# Phase_Measurements.net
KiCad netlist of a schematic drawn in Altium Designer
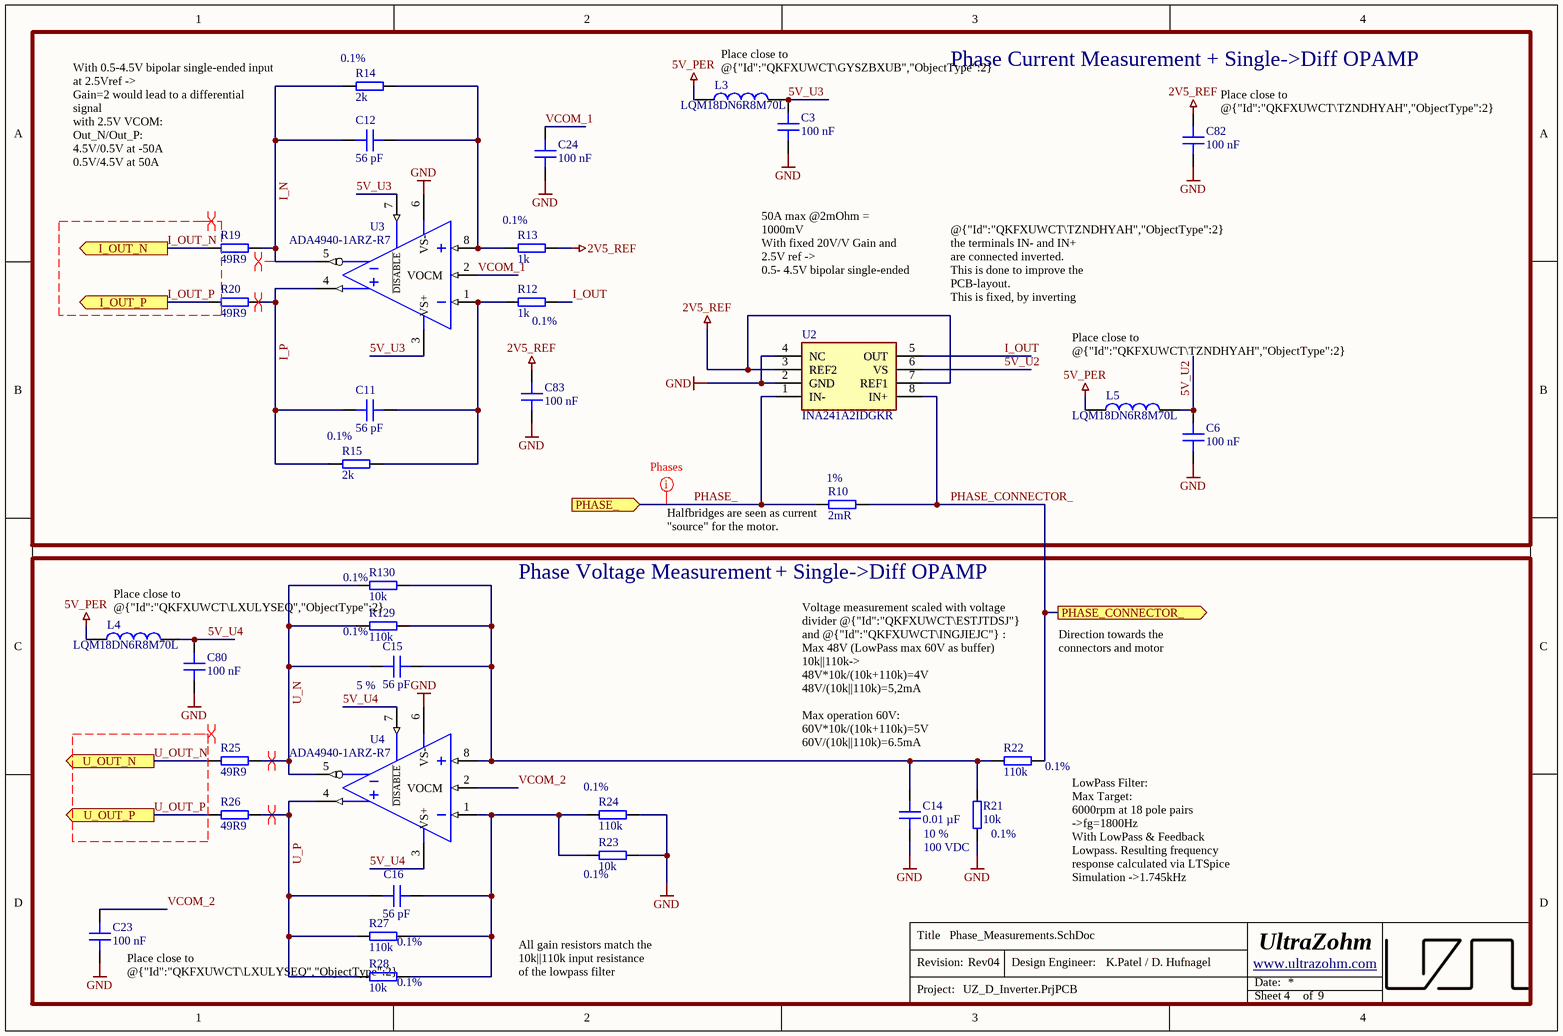
[diagram p0: Phase_Measurements.SchDoc]

(export (version "E")
  (design (tool "Eeschema 10.0.6"))
  (components
    (comp (ref "C3")
      (value "100 nF")
      (footprint "C_0603")
      (description "100V 100nF X7S ±10% 0603 Multilayer Ceramic Capacitors MLCC - SMD/SMT ROHS")
      (fields
        (field (name "MANUFACTURER PART NUMBER") "C1608X7S2A104KT000N")
        (field (name "MANUFACTURER") "TDK")
        (field (name "CREATED FROM") "AGeiger")
      )
      (libsource (lib "user") (part "Capacitor"))
    )
    (comp (ref "C6")
      (value "100 nF")
      (footprint "C_0603")
      (description "100V 100nF X7S ±10% 0603 Multilayer Ceramic Capacitors MLCC - SMD/SMT ROHS")
      (fields
        (field (name "MANUFACTURER PART NUMBER") "C1608X7S2A104KT000N")
        (field (name "MANUFACTURER") "TDK")
        (field (name "CREATED FROM") "AGeiger")
      )
      (libsource (lib "user") (part "Capacitor"))
    )
    (comp (ref "C11")
      (value "56 pF")
      (footprint "C_0603")
      (description "Capacitor 0603, 50 VDC, 56 pF, C0G")
      (fields
        (field (name "MANUFACTURER PART NUMBER") "CL10C560JB8NNNC")
        (field (name "MANUFACTURER") "Samsung Electro-Mechanics")
        (field (name "CREATED FROM") "DHufnagel")
      )
      (libsource (lib "user") (part "Capacitor"))
    )
    (comp (ref "C12")
      (value "56 pF")
      (footprint "C_0603")
      (description "Capacitor 0603, 50 VDC, 56 pF, C0G")
      (fields
        (field (name "MANUFACTURER PART NUMBER") "CL10C560JB8NNNC")
        (field (name "MANUFACTURER") "Samsung Electro-Mechanics")
        (field (name "CREATED FROM") "DHufnagel")
      )
      (libsource (lib "user") (part "Capacitor"))
    )
    (comp (ref "C14")
      (value "0.01 µF")
      (footprint "C_0805")
      (description "100V 10nF 0805 Multilayer Ceramic Capacitors MLCC - SMD/SMT ROHS")
      (fields
        (field (name "MANUFACTURER PART NUMBER") "HV0805X7R103K101NT")
        (field (name "MANUFACTURER") "AIDE")
        (field (name "TOLERANCE") "10 %")
        (field (name "VOLTAGE RATING") "100 VDC")
        (field (name "CREATED FROM") "KIlhan")
      )
      (libsource (lib "user") (part "Capacitor"))
    )
    (comp (ref "C15")
      (value "56 pF")
      (footprint "C_0603")
      (description "Capacitor 0603, 50 VDC, 56 pF, C0G")
      (fields
        (field (name "MANUFACTURER PART NUMBER") "CL10C560JB8NNNC")
        (field (name "MANUFACTURER") "Samsung Electro-Mechanics")
        (field (name "TOLERANCE") "5 %")
        (field (name "CREATED FROM") "DHufnagel")
      )
      (libsource (lib "user") (part "Capacitor"))
    )
    (comp (ref "C16")
      (value "56 pF")
      (footprint "C_0603")
      (description "Capacitor 0603, 50 VDC, 56 pF, C0G")
      (fields
        (field (name "MANUFACTURER PART NUMBER") "CL10C560JB8NNNC")
        (field (name "MANUFACTURER") "Samsung Electro-Mechanics")
        (field (name "CREATED FROM") "DHufnagel")
      )
      (libsource (lib "user") (part "Capacitor"))
    )
    (comp (ref "C23")
      (value "100 nF")
      (footprint "C_0603")
      (description "100V 100nF X7S ±10% 0603 Multilayer Ceramic Capacitors MLCC - SMD/SMT ROHS")
      (fields
        (field (name "MANUFACTURER PART NUMBER") "C1608X7S2A104KT000N")
        (field (name "MANUFACTURER") "TDK")
        (field (name "CREATED FROM") "AGeiger")
      )
      (libsource (lib "user") (part "Capacitor"))
    )
    (comp (ref "C24")
      (value "100 nF")
      (footprint "C_0603")
      (description "100V 100nF X7S ±10% 0603 Multilayer Ceramic Capacitors MLCC - SMD/SMT ROHS")
      (fields
        (field (name "MANUFACTURER PART NUMBER") "C1608X7S2A104KT000N")
        (field (name "MANUFACTURER") "TDK")
        (field (name "CREATED FROM") "AGeiger")
      )
      (libsource (lib "user") (part "Capacitor"))
    )
    (comp (ref "C80")
      (value "100 nF")
      (footprint "C_0603")
      (description "100V 100nF X7S ±10% 0603 Multilayer Ceramic Capacitors MLCC - SMD/SMT ROHS")
      (fields
        (field (name "MANUFACTURER PART NUMBER") "C1608X7S2A104KT000N")
        (field (name "MANUFACTURER") "TDK")
        (field (name "CREATED FROM") "AGeiger")
      )
      (libsource (lib "user") (part "Capacitor"))
    )
    (comp (ref "C82")
      (value "100 nF")
      (footprint "C_0603")
      (description "100V 100nF X7S ±10% 0603 Multilayer Ceramic Capacitors MLCC - SMD/SMT ROHS")
      (fields
        (field (name "MANUFACTURER PART NUMBER") "C1608X7S2A104KT000N")
        (field (name "MANUFACTURER") "TDK")
        (field (name "CREATED FROM") "AGeiger")
      )
      (libsource (lib "user") (part "Capacitor"))
    )
    (comp (ref "C83")
      (value "100 nF")
      (footprint "C_0603")
      (description "100V 100nF X7S ±10% 0603 Multilayer Ceramic Capacitors MLCC - SMD/SMT ROHS")
      (fields
        (field (name "MANUFACTURER PART NUMBER") "C1608X7S2A104KT000N")
        (field (name "MANUFACTURER") "TDK")
        (field (name "CREATED FROM") "AGeiger")
      )
      (libsource (lib "user") (part "Capacitor"))
    )
    (comp (ref "L3")
      (value "LQM18DN6R8M70L")
      (footprint "INDC1608X95N")
      (description "6.8µH, 120mA, 0603, 740mOhm, 20%")
      (fields
        (field (name "MF") "EPCOS / TDK")
        (field (name "MPN") "B82464G4154M")
        (field (name "CREATED FROM") "DHufnagel")
      )
      (libsource (lib "user") (part "B82464G4154M"))
    )
    (comp (ref "L4")
      (value "LQM18DN6R8M70L")
      (footprint "INDC1608X95N")
      (description "6.8µH, 120mA, 0603, 740mOhm, 20%")
      (fields
        (field (name "MF") "EPCOS / TDK")
        (field (name "MPN") "B82464G4154M")
        (field (name "CREATED FROM") "DHufnagel")
      )
      (libsource (lib "user") (part "B82464G4154M"))
    )
    (comp (ref "L5")
      (value "LQM18DN6R8M70L")
      (footprint "INDC1608X95N")
      (description "6.8µH, 120mA, 0603, 740mOhm, 20%")
      (fields
        (field (name "MF") "EPCOS / TDK")
        (field (name "MPN") "B82464G4154M")
        (field (name "CREATED FROM") "DHufnagel")
      )
      (libsource (lib "user") (part "B82464G4154M"))
    )
    (comp (ref "R10")
      (value "2mR")
      (footprint "3921")
      (description "Current Sense Resistors - SMD 3watts .002ohms 1%")
      (fields
        (field (name "MANUFACTURER PART NUMBER") "WSL39212L000FEA")
        (field (name "MANUFACTURER") "Vishay")
        (field (name "TOLERANCE") "1%")
        (field (name "CREATED FROM") "AGeiger")
      )
      (libsource (lib "user") (part "Resistor"))
    )
    (comp (ref "R12")
      (value "1k")
      (footprint "RES 0603_1608")
      (description "SMD resistor 0.1%")
      (fields
        (field (name "MANUFACTURER PART NUMBER") "PCF-W0603LF-03-1001-B-P-LT")
        (field (name "MANUFACTURER") "IRC / TT Electronics")
        (field (name "TOLERANCE") "0.1%")
        (field (name "CREATED FROM") "MGremer")
      )
      (libsource (lib "user") (part "Resistor"))
    )
    (comp (ref "R13")
      (value "1k")
      (footprint "RES 0603_1608")
      (description "SMD resistor 0.1%")
      (fields
        (field (name "MANUFACTURER PART NUMBER") "PCF-W0603LF-03-1001-B-P-LT")
        (field (name "MANUFACTURER") "IRC / TT Electronics")
        (field (name "TOLERANCE") "0.1%")
        (field (name "CREATED FROM") "MGremer")
      )
      (libsource (lib "user") (part "Resistor"))
    )
    (comp (ref "R14")
      (value "2k")
      (footprint "RES 0603_1608")
      (description "SMD resistor 0.1%")
      (fields
        (field (name "MANUFACTURER PART NUMBER") "ERJ-PB3B2001V")
        (field (name "MANUFACTURER") "Panasonic")
        (field (name "TOLERANCE") "0.1%")
        (field (name "CREATED FROM") "DHufnagel")
      )
      (libsource (lib "user") (part "Resistor"))
    )
    (comp (ref "R15")
      (value "2k")
      (footprint "RES 0603_1608")
      (description "SMD resistor 0.1%")
      (fields
        (field (name "MANUFACTURER PART NUMBER") "ERJ-PB3B2001V")
        (field (name "MANUFACTURER") "Panasonic")
        (field (name "TOLERANCE") "0.1%")
        (field (name "CREATED FROM") "DHufnagel")
      )
      (libsource (lib "user") (part "Resistor"))
    )
    (comp (ref "R19")
      (value "49R9")
      (footprint "RES 0603_1608")
      (description "SMD resistor 1%")
      (fields
        (field (name "MANUFACTURER PART NUMBER") "RK73H1JTTD49R9F")
        (field (name "MANUFACTURER") "KOA Speer")
        (field (name "CREATED FROM") "DHufnagel")
      )
      (libsource (lib "user") (part "Resistor"))
    )
    (comp (ref "R20")
      (value "49R9")
      (footprint "RES 0603_1608")
      (description "SMD resistor 1%")
      (fields
        (field (name "MANUFACTURER PART NUMBER") "RK73H1JTTD49R9F")
        (field (name "MANUFACTURER") "KOA Speer")
        (field (name "CREATED FROM") "DHufnagel")
      )
      (libsource (lib "user") (part "Resistor"))
    )
    (comp (ref "R21")
      (value "10k")
      (footprint "RES 0603_1608")
      (description "SMD resistor 0.1%, 10ppm")
      (fields
        (field (name "MANUFACTURER PART NUMBER") "RQ73C1J10KBTD")
        (field (name "MANUFACTURER") "TE Connectivity")
        (field (name "TOLERANCE") "0.1%")
        (field (name "CREATED FROM") "DHufnagel")
      )
      (libsource (lib "user") (part "Resistor"))
    )
    (comp (ref "R22")
      (value "110k")
      (footprint "RES 0603_1608")
      (description "SMD resistor 0.1%, 10ppm")
      (fields
        (field (name "MANUFACTURER PART NUMBER") "RQ73C1J110KBTD")
        (field (name "MANUFACTURER") "TE Connectivity / Holsworthy")
        (field (name "TOLERANCE") "0.1%")
        (field (name "CREATED FROM") "DHufnagel")
      )
      (libsource (lib "user") (part "Resistor"))
    )
    (comp (ref "R23")
      (value "10k")
      (footprint "RES 0603_1608")
      (description "SMD resistor 0.1%, 10ppm")
      (fields
        (field (name "MANUFACTURER PART NUMBER") "RQ73C1J10KBTD")
        (field (name "MANUFACTURER") "TE Connectivity")
        (field (name "TOLERANCE") "0.1%")
        (field (name "CREATED FROM") "DHufnagel")
      )
      (libsource (lib "user") (part "Resistor"))
    )
    (comp (ref "R24")
      (value "110k")
      (footprint "RES 0603_1608")
      (description "SMD resistor 0.1%, 10ppm")
      (fields
        (field (name "MANUFACTURER PART NUMBER") "RQ73C1J110KBTD")
        (field (name "MANUFACTURER") "TE Connectivity / Holsworthy")
        (field (name "TOLERANCE") "0.1%")
        (field (name "CREATED FROM") "DHufnagel")
      )
      (libsource (lib "user") (part "Resistor"))
    )
    (comp (ref "R25")
      (value "49R9")
      (footprint "RES 0603_1608")
      (description "SMD resistor 1%")
      (fields
        (field (name "MANUFACTURER PART NUMBER") "RK73H1JTTD49R9F")
        (field (name "MANUFACTURER") "KOA Speer")
        (field (name "CREATED FROM") "DHufnagel")
      )
      (libsource (lib "user") (part "Resistor"))
    )
    (comp (ref "R26")
      (value "49R9")
      (footprint "RES 0603_1608")
      (description "SMD resistor 1%")
      (fields
        (field (name "MANUFACTURER PART NUMBER") "RK73H1JTTD49R9F")
        (field (name "MANUFACTURER") "KOA Speer")
        (field (name "CREATED FROM") "DHufnagel")
      )
      (libsource (lib "user") (part "Resistor"))
    )
    (comp (ref "R27")
      (value "110k")
      (footprint "RES 0603_1608")
      (description "SMD resistor 0.1%, 10ppm")
      (fields
        (field (name "MANUFACTURER PART NUMBER") "RQ73C1J110KBTD")
        (field (name "MANUFACTURER") "TE Connectivity / Holsworthy")
        (field (name "TOLERANCE") "0.1%")
        (field (name "CREATED FROM") "DHufnagel")
      )
      (libsource (lib "user") (part "Resistor"))
    )
    (comp (ref "R28")
      (value "10k")
      (footprint "RES 0603_1608")
      (description "SMD resistor 0.1%, 10ppm")
      (fields
        (field (name "MANUFACTURER PART NUMBER") "RQ73C1J10KBTD")
        (field (name "MANUFACTURER") "TE Connectivity")
        (field (name "TOLERANCE") "0.1%")
        (field (name "CREATED FROM") "DHufnagel")
      )
      (libsource (lib "user") (part "Resistor"))
    )
    (comp (ref "R129")
      (value "110k")
      (footprint "RES 0603_1608")
      (description "SMD resistor 0.1%, 10ppm")
      (fields
        (field (name "MANUFACTURER PART NUMBER") "RQ73C1J110KBTD")
        (field (name "MANUFACTURER") "TE Connectivity / Holsworthy")
        (field (name "TOLERANCE") "0.1%")
        (field (name "CREATED FROM") "DHufnagel")
      )
      (libsource (lib "user") (part "Resistor"))
    )
    (comp (ref "R130")
      (value "10k")
      (footprint "RES 0603_1608")
      (description "SMD resistor 0.1%, 10ppm")
      (fields
        (field (name "MANUFACTURER PART NUMBER") "RQ73C1J10KBTD")
        (field (name "MANUFACTURER") "TE Connectivity")
        (field (name "TOLERANCE") "0.1%")
        (field (name "CREATED FROM") "DHufnagel")
      )
      (libsource (lib "user") (part "Resistor"))
    )
    (comp (ref "U2")
      (value "INA241A2IDGKR")
      (footprint "SOP65P490X110-8N")
      (description "Current Sense Amplifier, 5-100 V  CMV, 20 V/V, bidirectional")
      (fields (field (name "MANUFACTURER") "Texas Instruments") (field (name "CREATED FROM") "KPatel"))
      (libsource (lib "user") (part "INA241A2IDGKR"))
    )
    (comp (ref "U3")
      (value "ADA4940-1ARZ-R7")
      (footprint "SOT127P600X175-8N")
      (description "Fully Differential Amplifier, Ultralow-Power,Low Distortion, 260-MHz")
      (fields
        (field (name "MANUFACTURER") "Analog Devices")
        (field (name "LCSC PART NUMBER") "C730049")
        (field (name "CREATED FROM") "DHufnagel")
      )
      (libsource (lib "user") (part "ADA4940-1ARZ"))
    )
    (comp (ref "U4")
      (value "ADA4940-1ARZ-R7")
      (footprint "SOT127P600X175-8N")
      (description "Fully Differential Amplifier, Ultralow-Power,Low Distortion, 260-MHz")
      (fields
        (field (name "MANUFACTURER") "Analog Devices")
        (field (name "LCSC PART NUMBER") "C730049")
        (field (name "CREATED FROM") "DHufnagel")
      )
      (libsource (lib "user") (part "ADA4940-1ARZ"))
    )
  )
  (nets
    (net (code "1") (name "/5V_U2") (class "Default")
      (node (ref "C6") (pin "2") (pinfunction "2_2") (pintype "passive"))
      (node (ref "L5") (pin "2") (pinfunction "2_2") (pintype "passive"))
      (node (ref "U2") (pin "6") (pinfunction "VS_6") (pintype "passive"))
    )
    (net (code "2") (name "/5V_U3") (class "Default")
      (node (ref "C3") (pin "2") (pinfunction "2_2") (pintype "passive"))
      (node (ref "L3") (pin "2") (pinfunction "2_2") (pintype "passive"))
      (node (ref "U3") (pin "3") (pinfunction "VS+_3") (pintype "power_in"))
      (node (ref "U3") (pin "7") (pinfunction "~{DISABLE}_7") (pintype "input"))
    )
    (net (code "3") (name "/5V_U4") (class "Default")
      (node (ref "C80") (pin "2") (pinfunction "2_2") (pintype "passive"))
      (node (ref "L4") (pin "2") (pinfunction "2_2") (pintype "passive"))
      (node (ref "U4") (pin "3") (pinfunction "VS+_3") (pintype "power_in"))
      (node (ref "U4") (pin "7") (pinfunction "~{DISABLE}_7") (pintype "input"))
    )
    (net (code "4") (name "/I_N") (class "Default")
      (node (ref "C12") (pin "1") (pinfunction "1_1") (pintype "passive"))
      (node (ref "R14") (pin "1") (pinfunction "1_1") (pintype "passive"))
      (node (ref "R19") (pin "2") (pinfunction "2_2") (pintype "passive"))
      (node (ref "U3") (pin "5") (pinfunction "VOUT-_5") (pintype "output"))
    )
    (net (code "5") (name "/I_OUT") (class "Default")
      (node (ref "R12") (pin "2") (pinfunction "2_2") (pintype "passive"))
      (node (ref "U2") (pin "5") (pinfunction "OUT_5") (pintype "passive"))
    )
    (net (code "6") (name "/I_OUT_N") (class "Default")
      (node (ref "R19") (pin "1") (pinfunction "1_1") (pintype "passive"))
    )
    (net (code "7") (name "/I_OUT_P") (class "Default")
      (node (ref "R20") (pin "1") (pinfunction "1_1") (pintype "passive"))
    )
    (net (code "8") (name "/I_P") (class "Default")
      (node (ref "C11") (pin "1") (pinfunction "1_1") (pintype "passive"))
      (node (ref "R15") (pin "1") (pinfunction "1_1") (pintype "passive"))
      (node (ref "R20") (pin "2") (pinfunction "2_2") (pintype "passive"))
      (node (ref "U3") (pin "4") (pinfunction "VOUT+_4") (pintype "output"))
    )
    (net (code "9") (name "/PHASE_") (class "Default")
      (node (ref "R10") (pin "1") (pinfunction "1_1") (pintype "passive"))
      (node (ref "U2") (pin "1") (pinfunction "IN-_1") (pintype "passive"))
    )
    (net (code "10") (name "/PHASE_CONNECTOR_") (class "Default")
      (node (ref "R10") (pin "2") (pinfunction "2_2") (pintype "passive"))
      (node (ref "R22") (pin "2") (pinfunction "2_2") (pintype "passive"))
      (node (ref "U2") (pin "8") (pinfunction "IN+_8") (pintype "passive"))
    )
    (net (code "11") (name "/U_N") (class "Default")
      (node (ref "C15") (pin "1") (pinfunction "1_1") (pintype "passive"))
      (node (ref "R129") (pin "1") (pinfunction "1_1") (pintype "passive"))
      (node (ref "R130") (pin "2") (pinfunction "2_2") (pintype "passive"))
      (node (ref "R25") (pin "2") (pinfunction "2_2") (pintype "passive"))
      (node (ref "U4") (pin "5") (pinfunction "VOUT-_5") (pintype "output"))
    )
    (net (code "12") (name "/U_OUT_N") (class "Default")
      (node (ref "R25") (pin "1") (pinfunction "1_1") (pintype "passive"))
    )
    (net (code "13") (name "/U_OUT_P") (class "Default")
      (node (ref "R26") (pin "1") (pinfunction "1_1") (pintype "passive"))
    )
    (net (code "14") (name "/U_P") (class "Default")
      (node (ref "C16") (pin "1") (pinfunction "1_1") (pintype "passive"))
      (node (ref "R26") (pin "2") (pinfunction "2_2") (pintype "passive"))
      (node (ref "R27") (pin "1") (pinfunction "1_1") (pintype "passive"))
      (node (ref "R28") (pin "2") (pinfunction "2_2") (pintype "passive"))
      (node (ref "U4") (pin "4") (pinfunction "VOUT+_4") (pintype "output"))
    )
    (net (code "15") (name "/VCOM_1") (class "Default")
      (node (ref "C24") (pin "2") (pinfunction "2_2") (pintype "passive"))
      (node (ref "U3") (pin "2") (pinfunction "VOCM_2") (pintype "input"))
    )
    (net (code "16") (name "/VCOM_2") (class "Default")
      (node (ref "C23") (pin "2") (pinfunction "2_2") (pintype "passive"))
      (node (ref "U4") (pin "2") (pinfunction "VOCM_2") (pintype "input"))
    )
    (net (code "17") (name "2V5_REF") (class "Default")
      (node (ref "C82") (pin "2") (pinfunction "2_2") (pintype "passive"))
      (node (ref "C83") (pin "2") (pinfunction "2_2") (pintype "passive"))
      (node (ref "R13") (pin "2") (pinfunction "2_2") (pintype "passive"))
      (node (ref "U2") (pin "3") (pinfunction "REF2_3") (pintype "passive"))
      (node (ref "U2") (pin "7") (pinfunction "REF1_7") (pintype "passive"))
    )
    (net (code "18") (name "5V_PER") (class "Default")
      (node (ref "L3") (pin "1") (pinfunction "1_1") (pintype "passive"))
      (node (ref "L4") (pin "1") (pinfunction "1_1") (pintype "passive"))
      (node (ref "L5") (pin "1") (pinfunction "1_1") (pintype "passive"))
    )
    (net (code "19") (name "GND") (class "Default")
      (node (ref "C14") (pin "1") (pinfunction "1_1") (pintype "passive"))
      (node (ref "C23") (pin "1") (pinfunction "1_1") (pintype "passive"))
      (node (ref "C24") (pin "1") (pinfunction "1_1") (pintype "passive"))
      (node (ref "C3") (pin "1") (pinfunction "1_1") (pintype "passive"))
      (node (ref "C6") (pin "1") (pinfunction "1_1") (pintype "passive"))
      (node (ref "C80") (pin "1") (pinfunction "1_1") (pintype "passive"))
      (node (ref "C82") (pin "1") (pinfunction "1_1") (pintype "passive"))
      (node (ref "C83") (pin "1") (pinfunction "1_1") (pintype "passive"))
      (node (ref "R21") (pin "1") (pinfunction "1_1") (pintype "passive"))
      (node (ref "R23") (pin "1") (pinfunction "1_1") (pintype "passive"))
      (node (ref "R24") (pin "2") (pinfunction "2_2") (pintype "passive"))
      (node (ref "U2") (pin "2") (pinfunction "GND_2") (pintype "passive"))
      (node (ref "U2") (pin "4") (pinfunction "NC_4") (pintype "passive"))
      (node (ref "U3") (pin "6") (pinfunction "VS-_6") (pintype "power_in"))
      (node (ref "U4") (pin "6") (pinfunction "VS-_6") (pintype "power_in"))
    )
    (net (code "20") (name "Net-(U3-VIN+)") (class "Default")
      (node (ref "C12") (pin "2") (pinfunction "2_2") (pintype "passive"))
      (node (ref "R13") (pin "1") (pinfunction "1_1") (pintype "passive"))
      (node (ref "R14") (pin "2") (pinfunction "2_2") (pintype "passive"))
      (node (ref "U3") (pin "8") (pinfunction "VIN+_8") (pintype "input"))
    )
    (net (code "21") (name "Net-(U3-VIN-)") (class "Default")
      (node (ref "C11") (pin "2") (pinfunction "2_2") (pintype "passive"))
      (node (ref "R12") (pin "1") (pinfunction "1_1") (pintype "passive"))
      (node (ref "R15") (pin "2") (pinfunction "2_2") (pintype "passive"))
      (node (ref "U3") (pin "1") (pinfunction "VIN-_1") (pintype "input"))
    )
    (net (code "22") (name "Net-(U4-VIN+)") (class "Default")
      (node (ref "C14") (pin "2") (pinfunction "2_2") (pintype "passive"))
      (node (ref "C15") (pin "2") (pinfunction "2_2") (pintype "passive"))
      (node (ref "R129") (pin "2") (pinfunction "2_2") (pintype "passive"))
      (node (ref "R130") (pin "1") (pinfunction "1_1") (pintype "passive"))
      (node (ref "R21") (pin "2") (pinfunction "2_2") (pintype "passive"))
      (node (ref "R22") (pin "1") (pinfunction "1_1") (pintype "passive"))
      (node (ref "U4") (pin "8") (pinfunction "VIN+_8") (pintype "input"))
    )
    (net (code "23") (name "Net-(U4-VIN-)") (class "Default")
      (node (ref "C16") (pin "2") (pinfunction "2_2") (pintype "passive"))
      (node (ref "R23") (pin "2") (pinfunction "2_2") (pintype "passive"))
      (node (ref "R24") (pin "1") (pinfunction "1_1") (pintype "passive"))
      (node (ref "R27") (pin "2") (pinfunction "2_2") (pintype "passive"))
      (node (ref "R28") (pin "1") (pinfunction "1_1") (pintype "passive"))
      (node (ref "U4") (pin "1") (pinfunction "VIN-_1") (pintype "input"))
    )
  )
)
